# schema.net
KiCad netlist of a schematic drawn in EAGLE
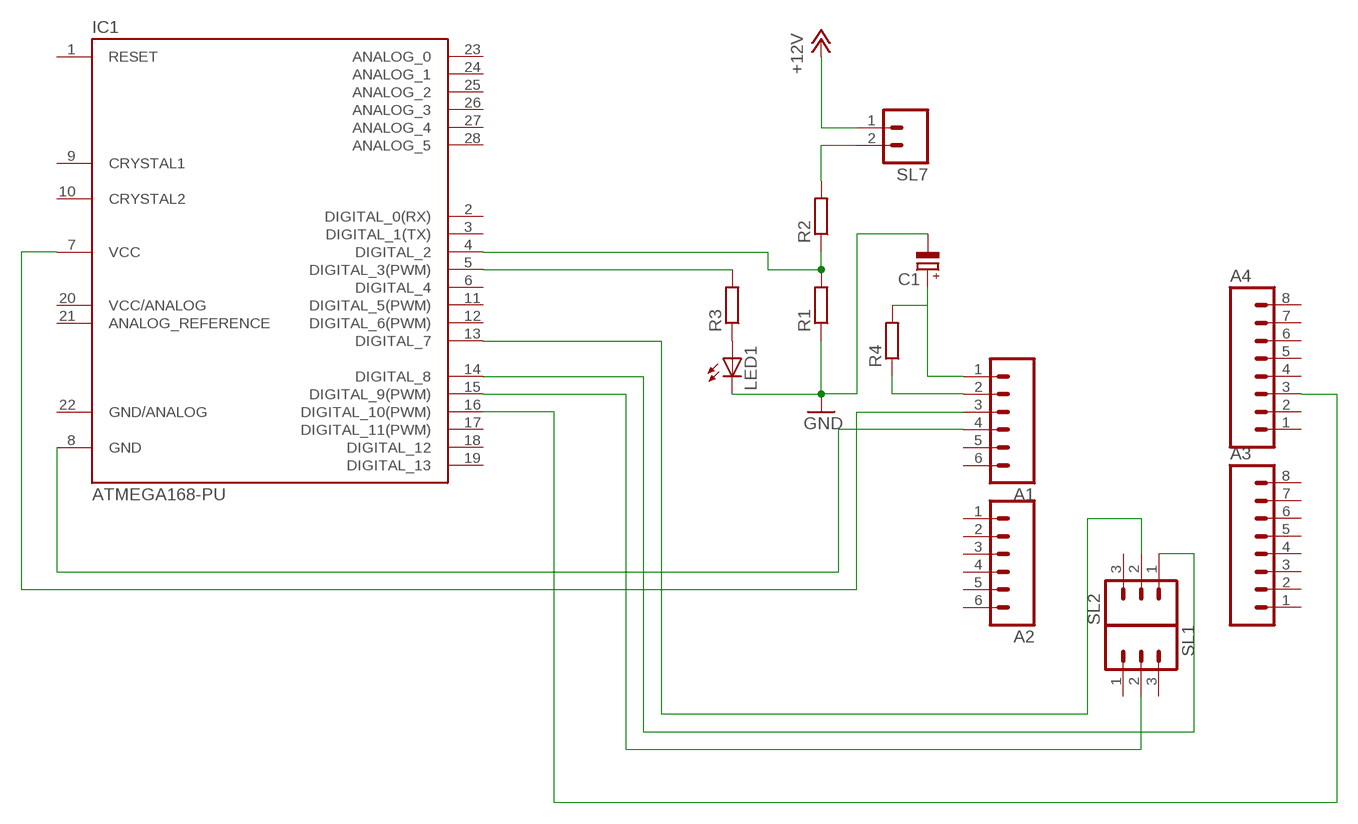
[diagram p0: schematic, sheet 1]

(export (version "E")
  (design (tool "Eeschema 10.0.6"))
  (components
    (comp (ref "A1")
      (value "M06")
      (footprint "eagle-import:06P")
      (libsource (lib "eagle-import") (part "M06"))
    )
    (comp (ref "A2")
      (value "M06")
      (footprint "eagle-import:06P")
      (libsource (lib "eagle-import") (part "M06"))
    )
    (comp (ref "A3")
      (value "M08")
      (footprint "eagle-import:08P")
      (libsource (lib "eagle-import") (part "M08"))
    )
    (comp (ref "A4")
      (value "M08")
      (footprint "eagle-import:08P")
      (libsource (lib "eagle-import") (part "M08"))
    )
    (comp (ref "C1")
      (value "CPOL-EUE2,5-6E")
      (footprint "eagle-import:E2,5-6E")
      (libsource (lib "eagle-import") (part "CPOL-EUE2,5-6E"))
    )
    (comp (ref "IC1")
      (value "ATMEGA168-PU")
      (footprint "eagle-import:DIL28-3")
      (libsource (lib "eagle-import") (part "ATMEGA168-PU"))
    )
    (comp (ref "LED1")
      (value "LED3MM")
      (footprint "eagle-import:LED3MM")
      (libsource (lib "eagle-import") (part "LED3MM"))
    )
    (comp (ref "R1")
      (value "R-EU_0207/7")
      (footprint "eagle-import:0207_7")
      (libsource (lib "eagle-import") (part "R-EU_0207/7"))
    )
    (comp (ref "R2")
      (value "R-EU_0207/7")
      (footprint "eagle-import:0207_7")
      (libsource (lib "eagle-import") (part "R-EU_0207/7"))
    )
    (comp (ref "R3")
      (value "R-EU_0207/7")
      (footprint "eagle-import:0207_7")
      (libsource (lib "eagle-import") (part "R-EU_0207/7"))
    )
    (comp (ref "R4")
      (value "R-EU_0207/7")
      (footprint "eagle-import:0207_7")
      (libsource (lib "eagle-import") (part "R-EU_0207/7"))
    )
    (comp (ref "SL1")
      (value "M03")
      (footprint "eagle-import:03P")
      (libsource (lib "eagle-import") (part "M03"))
    )
    (comp (ref "SL2")
      (value "M03")
      (footprint "eagle-import:03P")
      (libsource (lib "eagle-import") (part "M03"))
    )
    (comp (ref "SL7")
      (value "M02")
      (footprint "eagle-import:02P")
      (libsource (lib "eagle-import") (part "M02"))
    )
  )
  (nets
    (net (code "1") (name "+12V") (class "Default")
      (node (ref "SL7") (pin "1") (pinfunction "1_1") (pintype "passive"))
    )
    (net (code "2") (name "/GND{slash}ANALOG") (class "Default")
      (node (ref "IC1") (pin "22") (pinfunction "GND/ANALOG_22") (pintype "power_in"))
    )
    (net (code "3") (name "GND") (class "Default")
      (node (ref "C1") (pin "-") (pinfunction "-_-") (pintype "passive"))
      (node (ref "LED1") (pin "K") (pinfunction "C_K") (pintype "passive"))
      (node (ref "R1") (pin "1") (pinfunction "1_1") (pintype "passive"))
    )
    (net (code "4") (name "Net-(A1-Pad1)") (class "Default")
      (node (ref "A1") (pin "1") (pinfunction "1_1") (pintype "passive"))
      (node (ref "C1") (pin "+") (pinfunction "+_+") (pintype "passive"))
      (node (ref "R4") (pin "2") (pinfunction "2_2") (pintype "passive"))
    )
    (net (code "5") (name "Net-(A1-Pad2)") (class "Default")
      (node (ref "A1") (pin "2") (pinfunction "2_2") (pintype "passive"))
      (node (ref "R4") (pin "1") (pinfunction "1_1") (pintype "passive"))
    )
    (net (code "6") (name "Net-(IC1-DIGITAL_2)") (class "Default")
      (node (ref "IC1") (pin "4") (pinfunction "DIGITAL_2_4") (pintype "bidirectional"))
      (node (ref "R1") (pin "2") (pinfunction "2_2") (pintype "passive"))
      (node (ref "R2") (pin "1") (pinfunction "1_1") (pintype "passive"))
    )
    (net (code "7") (name "Net-(IC1-DIGITAL_3(PWM))") (class "Default")
      (node (ref "IC1") (pin "5") (pinfunction "DIGITAL_3(PWM)_5") (pintype "bidirectional"))
      (node (ref "R3") (pin "2") (pinfunction "2_2") (pintype "passive"))
    )
    (net (code "8") (name "Net-(IC1-DIGITAL_7)") (class "Default")
      (node (ref "IC1") (pin "13") (pinfunction "DIGITAL_7_13") (pintype "bidirectional"))
      (node (ref "SL2") (pin "2") (pinfunction "2_2") (pintype "passive"))
    )
    (net (code "9") (name "Net-(IC1-DIGITAL_8)") (class "Default")
      (node (ref "IC1") (pin "14") (pinfunction "DIGITAL_8_14") (pintype "bidirectional"))
      (node (ref "SL2") (pin "1") (pinfunction "1_1") (pintype "passive"))
    )
    (net (code "10") (name "Net-(IC1-DIGITAL_9(PWM))") (class "Default")
      (node (ref "IC1") (pin "15") (pinfunction "DIGITAL_9(PWM)_15") (pintype "bidirectional"))
      (node (ref "SL1") (pin "2") (pinfunction "2_2") (pintype "passive"))
    )
    (net (code "11") (name "Net-(IC1-DIGITAL_10(PWM))") (class "Default")
      (node (ref "A4") (pin "3") (pinfunction "3_3") (pintype "passive"))
      (node (ref "IC1") (pin "16") (pinfunction "DIGITAL_10(PWM)_16") (pintype "bidirectional"))
    )
    (net (code "12") (name "Net-(IC1-GND)") (class "Default")
      (node (ref "A1") (pin "4") (pinfunction "4_4") (pintype "passive"))
      (node (ref "IC1") (pin "8") (pinfunction "GND_8") (pintype "power_in"))
    )
    (net (code "13") (name "Net-(IC1-VCC)") (class "Default")
      (node (ref "A1") (pin "3") (pinfunction "3_3") (pintype "passive"))
      (node (ref "IC1") (pin "7") (pinfunction "VCC_7") (pintype "power_in"))
    )
    (net (code "14") (name "Net-(LED1-PadA)") (class "Default")
      (node (ref "LED1") (pin "A") (pinfunction "A_A") (pintype "passive"))
      (node (ref "R3") (pin "1") (pinfunction "1_1") (pintype "passive"))
    )
    (net (code "15") (name "Net-(R2-Pad2)") (class "Default")
      (node (ref "R2") (pin "2") (pinfunction "2_2") (pintype "passive"))
      (node (ref "SL7") (pin "2") (pinfunction "2_2") (pintype "passive"))
    )
    (net (code "16") (name "unconnected-(A1-Pad5)") (class "Default")
      (node (ref "A1") (pin "5") (pinfunction "5_5") (pintype "passive"))
    )
    (net (code "17") (name "unconnected-(A1-Pad6)") (class "Default")
      (node (ref "A1") (pin "6") (pinfunction "6_6") (pintype "passive"))
    )
    (net (code "18") (name "unconnected-(A2-Pad1)") (class "Default")
      (node (ref "A2") (pin "1") (pinfunction "1_1") (pintype "passive"))
    )
    (net (code "19") (name "unconnected-(A2-Pad2)") (class "Default")
      (node (ref "A2") (pin "2") (pinfunction "2_2") (pintype "passive"))
    )
    (net (code "20") (name "unconnected-(A2-Pad3)") (class "Default")
      (node (ref "A2") (pin "3") (pinfunction "3_3") (pintype "passive"))
    )
    (net (code "21") (name "unconnected-(A2-Pad4)") (class "Default")
      (node (ref "A2") (pin "4") (pinfunction "4_4") (pintype "passive"))
    )
    (net (code "22") (name "unconnected-(A2-Pad5)") (class "Default")
      (node (ref "A2") (pin "5") (pinfunction "5_5") (pintype "passive"))
    )
    (net (code "23") (name "unconnected-(A2-Pad6)") (class "Default")
      (node (ref "A2") (pin "6") (pinfunction "6_6") (pintype "passive"))
    )
    (net (code "24") (name "unconnected-(A3-Pad1)") (class "Default")
      (node (ref "A3") (pin "1") (pinfunction "1_1") (pintype "passive"))
    )
    (net (code "25") (name "unconnected-(A3-Pad2)") (class "Default")
      (node (ref "A3") (pin "2") (pinfunction "2_2") (pintype "passive"))
    )
    (net (code "26") (name "unconnected-(A3-Pad3)") (class "Default")
      (node (ref "A3") (pin "3") (pinfunction "3_3") (pintype "passive"))
    )
    (net (code "27") (name "unconnected-(A3-Pad4)") (class "Default")
      (node (ref "A3") (pin "4") (pinfunction "4_4") (pintype "passive"))
    )
    (net (code "28") (name "unconnected-(A3-Pad5)") (class "Default")
      (node (ref "A3") (pin "5") (pinfunction "5_5") (pintype "passive"))
    )
    (net (code "29") (name "unconnected-(A3-Pad6)") (class "Default")
      (node (ref "A3") (pin "6") (pinfunction "6_6") (pintype "passive"))
    )
    (net (code "30") (name "unconnected-(A3-Pad7)") (class "Default")
      (node (ref "A3") (pin "7") (pinfunction "7_7") (pintype "passive"))
    )
    (net (code "31") (name "unconnected-(A3-Pad8)") (class "Default")
      (node (ref "A3") (pin "8") (pinfunction "8_8") (pintype "passive"))
    )
    (net (code "32") (name "unconnected-(A4-Pad1)") (class "Default")
      (node (ref "A4") (pin "1") (pinfunction "1_1") (pintype "passive"))
    )
    (net (code "33") (name "unconnected-(A4-Pad2)") (class "Default")
      (node (ref "A4") (pin "2") (pinfunction "2_2") (pintype "passive"))
    )
    (net (code "34") (name "unconnected-(A4-Pad4)") (class "Default")
      (node (ref "A4") (pin "4") (pinfunction "4_4") (pintype "passive"))
    )
    (net (code "35") (name "unconnected-(A4-Pad5)") (class "Default")
      (node (ref "A4") (pin "5") (pinfunction "5_5") (pintype "passive"))
    )
    (net (code "36") (name "unconnected-(A4-Pad6)") (class "Default")
      (node (ref "A4") (pin "6") (pinfunction "6_6") (pintype "passive"))
    )
    (net (code "37") (name "unconnected-(A4-Pad7)") (class "Default")
      (node (ref "A4") (pin "7") (pinfunction "7_7") (pintype "passive"))
    )
    (net (code "38") (name "unconnected-(A4-Pad8)") (class "Default")
      (node (ref "A4") (pin "8") (pinfunction "8_8") (pintype "passive"))
    )
    (net (code "39") (name "unconnected-(IC1-ANALOG_0-Pad23)") (class "Default")
      (node (ref "IC1") (pin "23") (pinfunction "ANALOG_0_23") (pintype "bidirectional"))
    )
    (net (code "40") (name "unconnected-(IC1-ANALOG_1-Pad24)") (class "Default")
      (node (ref "IC1") (pin "24") (pinfunction "ANALOG_1_24") (pintype "bidirectional"))
    )
    (net (code "41") (name "unconnected-(IC1-ANALOG_2-Pad25)") (class "Default")
      (node (ref "IC1") (pin "25") (pinfunction "ANALOG_2_25") (pintype "bidirectional"))
    )
    (net (code "42") (name "unconnected-(IC1-ANALOG_3-Pad26)") (class "Default")
      (node (ref "IC1") (pin "26") (pinfunction "ANALOG_3_26") (pintype "bidirectional"))
    )
    (net (code "43") (name "unconnected-(IC1-ANALOG_4-Pad27)") (class "Default")
      (node (ref "IC1") (pin "27") (pinfunction "ANALOG_4_27") (pintype "bidirectional"))
    )
    (net (code "44") (name "unconnected-(IC1-ANALOG_5-Pad28)") (class "Default")
      (node (ref "IC1") (pin "28") (pinfunction "ANALOG_5_28") (pintype "bidirectional"))
    )
    (net (code "45") (name "unconnected-(IC1-ANALOG_REFERENCE-Pad21)") (class "Default")
      (node (ref "IC1") (pin "21") (pinfunction "ANALOG_REFERENCE_21") (pintype "passive"))
    )
    (net (code "46") (name "unconnected-(IC1-CRYSTAL1-Pad9)") (class "Default")
      (node (ref "IC1") (pin "9") (pinfunction "CRYSTAL1_9") (pintype "bidirectional"))
    )
    (net (code "47") (name "unconnected-(IC1-CRYSTAL2-Pad10)") (class "Default")
      (node (ref "IC1") (pin "10") (pinfunction "CRYSTAL2_10") (pintype "bidirectional"))
    )
    (net (code "48") (name "unconnected-(IC1-DIGITAL_0(RX)-Pad2)") (class "Default")
      (node (ref "IC1") (pin "2") (pinfunction "DIGITAL_0(RX)_2") (pintype "bidirectional"))
    )
    (net (code "49") (name "unconnected-(IC1-DIGITAL_1(TX)-Pad3)") (class "Default")
      (node (ref "IC1") (pin "3") (pinfunction "DIGITAL_1(TX)_3") (pintype "bidirectional"))
    )
    (net (code "50") (name "unconnected-(IC1-DIGITAL_4-Pad6)") (class "Default")
      (node (ref "IC1") (pin "6") (pinfunction "DIGITAL_4_6") (pintype "bidirectional"))
    )
    (net (code "51") (name "unconnected-(IC1-DIGITAL_5(PWM)-Pad11)") (class "Default")
      (node (ref "IC1") (pin "11") (pinfunction "DIGITAL_5(PWM)_11") (pintype "bidirectional"))
    )
    (net (code "52") (name "unconnected-(IC1-DIGITAL_6(PWM)-Pad12)") (class "Default")
      (node (ref "IC1") (pin "12") (pinfunction "DIGITAL_6(PWM)_12") (pintype "bidirectional"))
    )
    (net (code "53") (name "unconnected-(IC1-DIGITAL_11(PWM)-Pad17)") (class "Default")
      (node (ref "IC1") (pin "17") (pinfunction "DIGITAL_11(PWM)_17") (pintype "bidirectional"))
    )
    (net (code "54") (name "unconnected-(IC1-DIGITAL_12-Pad18)") (class "Default")
      (node (ref "IC1") (pin "18") (pinfunction "DIGITAL_12_18") (pintype "bidirectional"))
    )
    (net (code "55") (name "unconnected-(IC1-DIGITAL_13-Pad19)") (class "Default")
      (node (ref "IC1") (pin "19") (pinfunction "DIGITAL_13_19") (pintype "bidirectional"))
    )
    (net (code "56") (name "unconnected-(IC1-RESET-Pad1)") (class "Default")
      (node (ref "IC1") (pin "1") (pinfunction "RESET_1") (pintype "bidirectional"))
    )
    (net (code "57") (name "unconnected-(IC1-VCC{slash}ANALOG-Pad20)") (class "Default")
      (node (ref "IC1") (pin "20") (pinfunction "VCC/ANALOG_20") (pintype "passive"))
    )
    (net (code "58") (name "unconnected-(SL1-Pad1)") (class "Default")
      (node (ref "SL1") (pin "1") (pinfunction "1_1") (pintype "passive"))
    )
    (net (code "59") (name "unconnected-(SL1-Pad3)") (class "Default")
      (node (ref "SL1") (pin "3") (pinfunction "3_3") (pintype "passive"))
    )
    (net (code "60") (name "unconnected-(SL2-Pad3)") (class "Default")
      (node (ref "SL2") (pin "3") (pinfunction "3_3") (pintype "passive"))
    )
  )
)
